# Sensirion_connector_board_v002.net
KiCad netlist of a schematic drawn in EAGLE
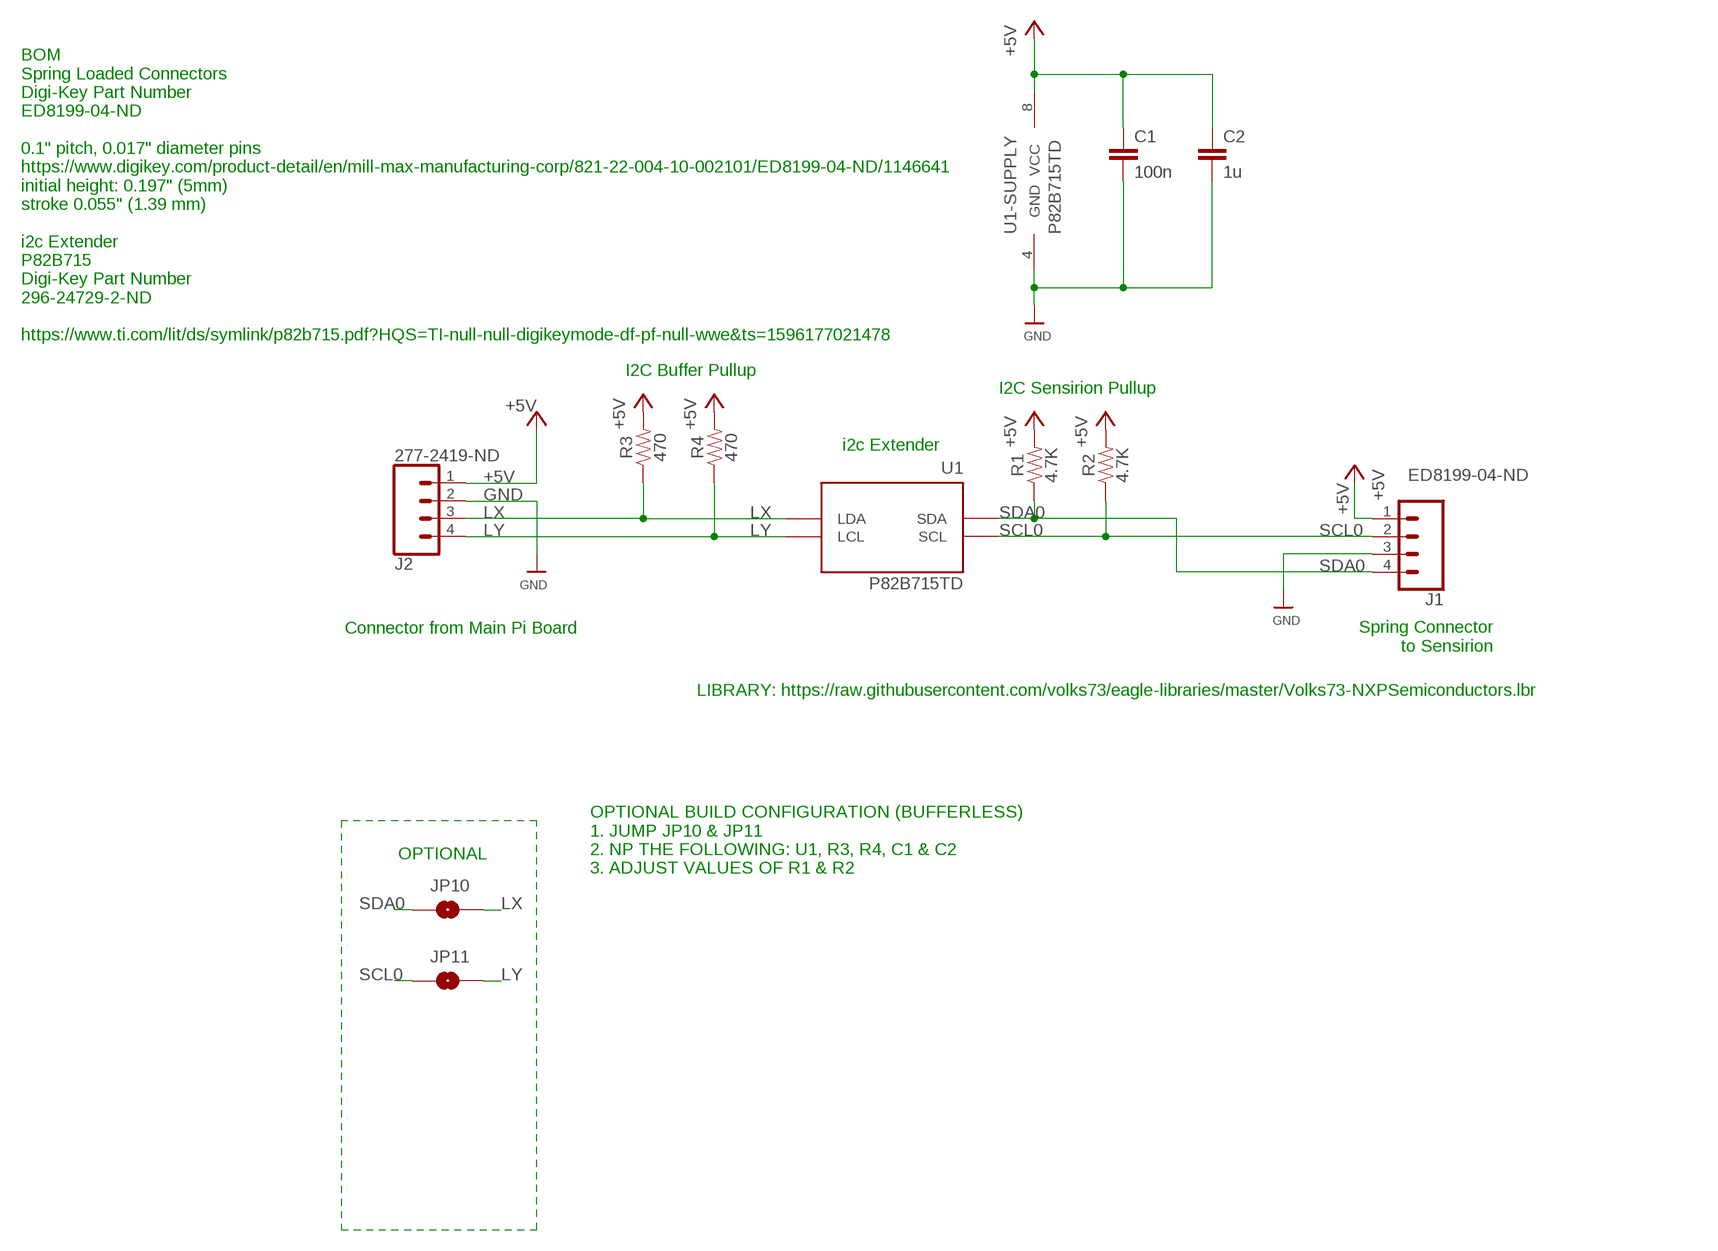
[diagram p0: schematic, sheet 1]

(export (version "E")
  (design (tool "Eeschema 10.0.6"))
  (components
    (comp (ref "C1")
      (value "100n")
      (footprint "eagle-import:0805")
      (libsource (lib "eagle-import") (part "CAP-0805"))
    )
    (comp (ref "C2")
      (value "1u")
      (footprint "eagle-import:0805")
      (libsource (lib "eagle-import") (part "CAP-0805"))
    )
    (comp (ref "J1")
      (value "ED8199-04-ND")
      (footprint "eagle-import:1X04_30MILL_DIA")
      (libsource (lib "eagle-import") (part "CONN_0430MILL_DIA"))
    )
    (comp (ref "J2")
      (value "277-2419-ND")
      (footprint "eagle-import:1X04_3.5MM_RA")
      (libsource (lib "eagle-import") (part "CONN_043.5MM_RA"))
    )
    (comp (ref "JP10")
      (value "JUMPER-SMT_2_NO_SILK")
      (footprint "eagle-import:SMT-JUMPER_2_NO_SILK")
      (libsource (lib "eagle-import") (part "JUMPER-SMT_2_NO_SILK"))
    )
    (comp (ref "JP11")
      (value "JUMPER-SMT_2_NO_SILK")
      (footprint "eagle-import:SMT-JUMPER_2_NO_SILK")
      (libsource (lib "eagle-import") (part "JUMPER-SMT_2_NO_SILK"))
    )
    (comp (ref "R1")
      (value "4.7K")
      (footprint "eagle-import:0805")
      (libsource (lib "eagle-import") (part "0.3OHM-0805-1/8W-1%"))
    )
    (comp (ref "R2")
      (value "4.7K")
      (footprint "eagle-import:0805")
      (libsource (lib "eagle-import") (part "0.3OHM-0805-1/8W-1%"))
    )
    (comp (ref "R3")
      (value "470")
      (footprint "eagle-import:0805")
      (libsource (lib "eagle-import") (part "0.3OHM-0805-1/8W-1%"))
    )
    (comp (ref "R4")
      (value "470")
      (footprint "eagle-import:0805")
      (libsource (lib "eagle-import") (part "0.3OHM-0805-1/8W-1%"))
    )
    (comp (ref "U1")
      (value "P82B715TD")
      (footprint "eagle-import:SOIC-8")
      (fields (field (name "MANUFACTURER") "NXP Semiconductors") (field (name "PART_NUMBER") "P82B715TD,118"))
      (libsource (lib "eagle-import") (part "P82B715?TD"))
    )
  )
  (nets
    (net (code "1") (name "+5V") (class "Default")
      (node (ref "C1") (pin "1") (pinfunction "1_1") (pintype "passive"))
      (node (ref "C2") (pin "1") (pinfunction "1_1") (pintype "passive"))
      (node (ref "J1") (pin "1") (pinfunction "1_1") (pintype "passive"))
      (node (ref "J2") (pin "1") (pinfunction "1_1") (pintype "passive"))
      (node (ref "R1") (pin "2") (pinfunction "2_2") (pintype "passive"))
      (node (ref "R2") (pin "2") (pinfunction "2_2") (pintype "passive"))
      (node (ref "R3") (pin "2") (pinfunction "2_2") (pintype "passive"))
      (node (ref "R4") (pin "2") (pinfunction "2_2") (pintype "passive"))
      (node (ref "U1") (pin "8") (pinfunction "VCC_8") (pintype "bidirectional"))
    )
    (net (code "2") (name "/LX") (class "Default")
      (node (ref "J2") (pin "3") (pinfunction "3_3") (pintype "passive"))
      (node (ref "JP10") (pin "2") (pinfunction "2_2") (pintype "passive"))
      (node (ref "R3") (pin "1") (pinfunction "1_1") (pintype "passive"))
      (node (ref "U1") (pin "7") (pinfunction "LDA_7") (pintype "bidirectional"))
    )
    (net (code "3") (name "/LY") (class "Default")
      (node (ref "J2") (pin "4") (pinfunction "4_4") (pintype "passive"))
      (node (ref "JP11") (pin "2") (pinfunction "2_2") (pintype "passive"))
      (node (ref "R4") (pin "1") (pinfunction "1_1") (pintype "passive"))
      (node (ref "U1") (pin "2") (pinfunction "LCL_2") (pintype "bidirectional"))
    )
    (net (code "4") (name "/SCL0") (class "Default")
      (node (ref "J1") (pin "2") (pinfunction "2_2") (pintype "passive"))
      (node (ref "JP11") (pin "1") (pinfunction "1_1") (pintype "passive"))
      (node (ref "R2") (pin "1") (pinfunction "1_1") (pintype "passive"))
      (node (ref "U1") (pin "3") (pinfunction "SCL_3") (pintype "bidirectional"))
    )
    (net (code "5") (name "/SDA0") (class "Default")
      (node (ref "J1") (pin "4") (pinfunction "4_4") (pintype "passive"))
      (node (ref "JP10") (pin "1") (pinfunction "1_1") (pintype "passive"))
      (node (ref "R1") (pin "1") (pinfunction "1_1") (pintype "passive"))
      (node (ref "U1") (pin "6") (pinfunction "SDA_6") (pintype "bidirectional"))
    )
    (net (code "6") (name "GND") (class "Default")
      (node (ref "C1") (pin "2") (pinfunction "2_2") (pintype "passive"))
      (node (ref "C2") (pin "2") (pinfunction "2_2") (pintype "passive"))
      (node (ref "J1") (pin "3") (pinfunction "3_3") (pintype "passive"))
      (node (ref "J2") (pin "2") (pinfunction "2_2") (pintype "passive"))
      (node (ref "U1") (pin "4") (pinfunction "GND_4") (pintype "bidirectional"))
    )
  )
)
